# DST800_NMEA2k-CAN_Indicator.net
KiCad netlist of a schematic drawn in Altium Designer
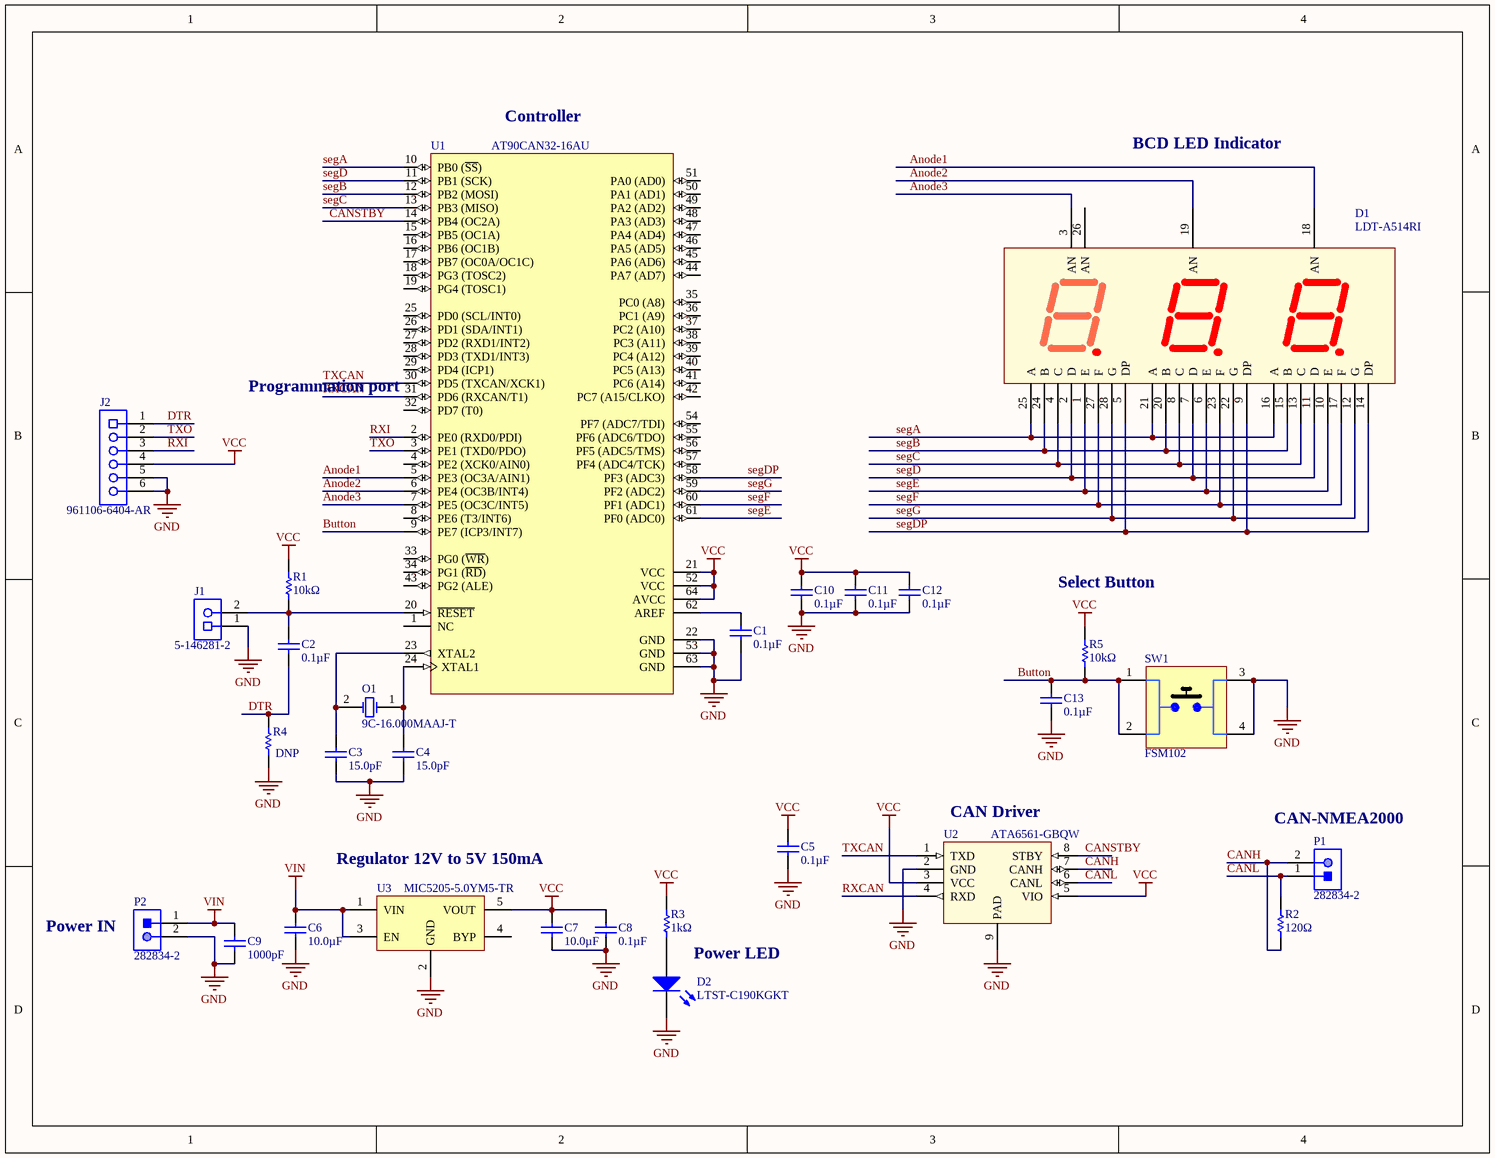
[diagram p0: DST800_NMEA2k-CAN_Indicator.SchDoc]

(export (version "E")
  (design (tool "Eeschema 10.0.6"))
  (components
    (comp (ref "C1")
      (value "0.1µF")
      (footprint "PCB-mhhqftc5ilnrg4qi8ds6-1")
      (description "CAP CER 0.1uF 50V X7R 0603")
      (fields
        (field (name "MANUFACTURER") "Samsung Electro-Mechanics")
        (field (name "MANUFACTURERPARTNUMBER") "CL10B104KB8NNNC")
      )
      (libsource (lib "DST800_NMEA2k-CAN_Indicator") (part "CMP-1af8d38ac64bc53f-5"))
    )
    (comp (ref "C2")
      (value "0.1µF")
      (footprint "PCB-mhhqftc5ilnrg4qi8ds6-1")
      (description "CAP CER 0.1uF 50V X7R 0603")
      (fields
        (field (name "MANUFACTURER") "Samsung Electro-Mechanics")
        (field (name "MANUFACTURERPARTNUMBER") "CL10B104KB8NNNC")
      )
      (libsource (lib "DST800_NMEA2k-CAN_Indicator") (part "CMP-1af8d38ac64bc53f-5"))
    )
    (comp (ref "C3")
      (value "15.0pF")
      (footprint "PCB-69ec8bfnjhyebnpbrrfx-1")
      (description "CAP CER 15pF ±5% 50V C0G/NP0 0603 [1608]")
      (fields
        (field (name "MANUFACTURER") "TDK")
        (field (name "MANUFACTURERPARTNUMBER") "C1608C0G1H150J080AA")
      )
      (libsource (lib "DST800_NMEA2k-CAN_Indicator") (part "CMP-57259fa49f8088e2-2"))
    )
    (comp (ref "C4")
      (value "15.0pF")
      (footprint "PCB-69ec8bfnjhyebnpbrrfx-1")
      (description "CAP CER 15pF ±5% 50V C0G/NP0 0603 [1608]")
      (fields
        (field (name "MANUFACTURER") "TDK")
        (field (name "MANUFACTURERPARTNUMBER") "C1608C0G1H150J080AA")
      )
      (libsource (lib "DST800_NMEA2k-CAN_Indicator") (part "CMP-57259fa49f8088e2-2"))
    )
    (comp (ref "C5")
      (value "0.1µF")
      (footprint "PCB-mhhqftc5ilnrg4qi8ds6-1")
      (description "CAP CER 0.1uF 50V X7R 0603")
      (fields
        (field (name "MANUFACTURER") "Samsung Electro-Mechanics")
        (field (name "MANUFACTURERPARTNUMBER") "CL10B104KB8NNNC")
      )
      (libsource (lib "DST800_NMEA2k-CAN_Indicator") (part "CMP-1af8d38ac64bc53f-5"))
    )
    (comp (ref "C6")
      (value "10.0µF")
      (footprint "PCB-j0jk5xr8qbnaskonccg4-1")
      (description "CAP CER 10uF ±10% 25V X7R 1210")
      (fields
        (field (name "MANUFACTURER") "TDK")
        (field (name "MANUFACTURERPARTNUMBER") "C3225X7R1E106K250AC")
      )
      (libsource (lib "DST800_NMEA2k-CAN_Indicator") (part "CMP-2bdce35de069f41b-1"))
    )
    (comp (ref "C7")
      (value "10.0µF")
      (footprint "PCB-j0jk5xr8qbnaskonccg4-1")
      (description "CAP CER 10uF ±10% 25V X7R 1210")
      (fields
        (field (name "MANUFACTURER") "TDK")
        (field (name "MANUFACTURERPARTNUMBER") "C3225X7R1E106K250AC")
      )
      (libsource (lib "DST800_NMEA2k-CAN_Indicator") (part "CMP-2bdce35de069f41b-1"))
    )
    (comp (ref "C8")
      (value "0.1µF")
      (footprint "PCB-mhhqftc5ilnrg4qi8ds6-1")
      (description "CAP CER 0.1uF 50V X7R 0603")
      (fields
        (field (name "MANUFACTURER") "Samsung Electro-Mechanics")
        (field (name "MANUFACTURERPARTNUMBER") "CL10B104KB8NNNC")
      )
      (libsource (lib "DST800_NMEA2k-CAN_Indicator") (part "CMP-1af8d38ac64bc53f-5"))
    )
    (comp (ref "C9")
      (value "1000pF")
      (footprint "CAPC1608X90X35LL15T15")
      (description "CAP CER 1000pF ±20% 100V X7R 0603")
      (fields (field (name "MANUFACTURERPARTNUMBER") "06031C102MAT2A") (field (name "MANUFACTURER") "AVX"))
      (libsource (lib "DST800_NMEA2k-CAN_Indicator") (part "CMP-126202-2"))
    )
    (comp (ref "C10")
      (value "0.1µF")
      (footprint "PCB-mhhqftc5ilnrg4qi8ds6-1")
      (description "CAP CER 0.1uF 50V X7R 0603")
      (fields
        (field (name "MANUFACTURER") "Samsung Electro-Mechanics")
        (field (name "MANUFACTURERPARTNUMBER") "CL10B104KB8NNNC")
      )
      (libsource (lib "DST800_NMEA2k-CAN_Indicator") (part "CMP-1af8d38ac64bc53f-5"))
    )
    (comp (ref "C11")
      (value "0.1µF")
      (footprint "PCB-mhhqftc5ilnrg4qi8ds6-1")
      (description "CAP CER 0.1uF 50V X7R 0603")
      (fields
        (field (name "MANUFACTURER") "Samsung Electro-Mechanics")
        (field (name "MANUFACTURERPARTNUMBER") "CL10B104KB8NNNC")
      )
      (libsource (lib "DST800_NMEA2k-CAN_Indicator") (part "CMP-1af8d38ac64bc53f-5"))
    )
    (comp (ref "C12")
      (value "0.1µF")
      (footprint "PCB-mhhqftc5ilnrg4qi8ds6-1")
      (description "CAP CER 0.1uF 50V X7R 0603")
      (fields
        (field (name "MANUFACTURER") "Samsung Electro-Mechanics")
        (field (name "MANUFACTURERPARTNUMBER") "CL10B104KB8NNNC")
      )
      (libsource (lib "DST800_NMEA2k-CAN_Indicator") (part "CMP-1af8d38ac64bc53f-5"))
    )
    (comp (ref "C13")
      (value "0.1µF")
      (footprint "PCB-mhhqftc5ilnrg4qi8ds6-1")
      (description "CAP CER 0.1uF 50V X7R 0603")
      (fields
        (field (name "MANUFACTURER") "Samsung Electro-Mechanics")
        (field (name "MANUFACTURERPARTNUMBER") "CL10B104KB8NNNC")
      )
      (libsource (lib "DST800_NMEA2k-CAN_Indicator") (part "CMP-1af8d38ac64bc53f-5"))
    )
    (comp (ref "D1")
      (value "LDT-A514RI")
      (footprint "LDTA514RI")
      (description "Display 3-digit 7-Seg 0.56 in")
      (fields (field (name "MANUFACTURER") "Lumex"))
      (libsource (lib "DST800_NMEA2k-CAN_Indicator") (part "CMP-6dbba4b18441b27c-1"))
    )
    (comp (ref "D2")
      (value "LTST-C190KGKT")
      (footprint "PCB-eapfwhp0rnksgujf96h3-1")
      (description "LED 0603 green")
      (fields (field (name "MANUFACTURER") "Lite-On"))
      (libsource (lib "DST800_NMEA2k-CAN_Indicator") (part "CMP-e1642866a00b3ea3-3"))
    )
    (comp (ref "J1")
      (value "5-146281-2")
      (footprint "PCB-angfy19quc8nc8nc7d0m-1")
      (description "CONN HEADER VERT 2POS Single 0.1in pitch")
      (fields (field (name "MANUFACTURER") "TE Connectivity"))
      (libsource (lib "DST800_NMEA2k-CAN_Indicator") (part "CMP-39c9f206a0b6e60e-14"))
    )
    (comp (ref "J2")
      (value "961106-6404-AR")
      (footprint "PCB-660833-1")
      (description "CONN HEADER VERT 6POS Single 0.1in pitch")
      (fields (field (name "MANUFACTURER") "3M"))
      (libsource (lib "DST800_NMEA2k-CAN_Indicator") (part "CMP-660833-2"))
    )
    (comp (ref "O1")
      (value "9C-16.000MAAJ-T")
      (footprint "PCB-3qvzojcyidn2gltqqmbl-1")
      (description "Crystal 16MHz 30ppm  18pF  HC-49/S SMD")
      (fields (field (name "MANUFACTURER") "TXC CORPORATION"))
      (libsource (lib "DST800_NMEA2k-CAN_Indicator") (part "CMP-df271731c43900e0-3"))
    )
    (comp (ref "P1")
      (value "282834-2")
      (footprint "PCB-0kdx5sneyudsmu18l6zv-1")
      (description "CONN Terminal Block; 16-30 AWG 0.197 in")
      (fields (field (name "MANUFACTURER") "TE Connectivity"))
      (libsource (lib "DST800_NMEA2k-CAN_Indicator") (part "CMP-369bfdc835bbe95c-32"))
    )
    (comp (ref "P2")
      (value "282834-2")
      (footprint "PCB-0kdx5sneyudsmu18l6zv-1")
      (description "CONN Terminal Block; 16-30 AWG 0.197 in")
      (fields (field (name "MANUFACTURER") "TE Connectivity"))
      (libsource (lib "") (part "CMP-369bfdc835bbe95c-32_1"))
    )
    (comp (ref "R1")
      (value "10kΩ")
      (footprint "RESC1608X55X30NL15T15")
      (description "RES 10K 1% 0.1W 0603")
      (fields
        (field (name "MANUFACTURERPARTNUMBER") "CRG0603F10K")
        (field (name "MANUFACTURER") "TE Connectivity")
      )
      (libsource (lib "DST800_NMEA2k-CAN_Indicator") (part "CMP-584891b72cc4878f-2"))
    )
    (comp (ref "R2")
      (value "120Ω")
      (footprint "RESC3216X60X45LL10T20")
      (description "RES Thick Film 120ohm 5% 1/4W 1206")
      (fields
        (field (name "MANUFACTURERPARTNUMBER") "CRCW1206120RJNEA")
        (field (name "MANUFACTURER") "Vishay")
      )
      (libsource (lib "DST800_NMEA2k-CAN_Indicator") (part "CMP-1858100-4"))
    )
    (comp (ref "R3")
      (value "1kΩ")
      (footprint "RESC1608X55X30NL20T20")
      (description "RES Metal Film 1Kohm 0.1%  0603")
      (fields
        (field (name "MANUFACTURERPARTNUMBER") "ERA-3YEB102V")
        (field (name "MANUFACTURER") "Panasonic")
      )
      (libsource (lib "DST800_NMEA2k-CAN_Indicator") (part "CMP-3717598-2"))
    )
    (comp (ref "R4")
      (value "DNP")
      (footprint "RESC1608X55X30NL20T20")
      (description "RES Metal Film 1Kohm 0.1%  0603")
      (fields
        (field (name "MANUFACTURERPARTNUMBER") "ERA-3YEB102V")
        (field (name "MANUFACTURER") "Panasonic")
      )
      (libsource (lib "DST800_NMEA2k-CAN_Indicator") (part "CMP-3717598-2"))
    )
    (comp (ref "R5")
      (value "10kΩ")
      (footprint "RESC1608X55X30NL15T15")
      (description "RES 10K 1% 0.1W 0603")
      (fields
        (field (name "MANUFACTURERPARTNUMBER") "CRG0603F10K")
        (field (name "MANUFACTURER") "TE Connectivity")
      )
      (libsource (lib "DST800_NMEA2k-CAN_Indicator") (part "CMP-584891b72cc4878f-2"))
    )
    (comp (ref "SW1")
      (value "FSM102")
      (footprint "PCB-8ps4wla3pj92cxv2yuvu-1")
      (description "PUSHBUTTON Momentary Tactile SPST Thru-Hole")
      (fields (field (name "MANUFACTURER") "TE Connectivity"))
      (libsource (lib "DST800_NMEA2k-CAN_Indicator") (part "CMP-43e488b0e8c29c23-11"))
    )
    (comp (ref "U1")
      (value "AT90CAN32-16AU")
      (footprint "64A_L")
      (description "IC Microcontroller 8-bit AVR 32KB Flash CAN Controller 53GPIO 64-pin LQFP")
      (fields (field (name "MANUFACTURER") "Microchip"))
      (libsource (lib "DST800_NMEA2k-CAN_Indicator") (part "CMP-972593-3"))
    )
    (comp (ref "U2")
      (value "ATA6561-GBQW")
      (footprint "PCB_8-PinVDFN")
      (description "IC Transeiver CAN 5Mbps 8-Pin VDFN EP")
      (fields (field (name "MANUFACTURER") "Microchip"))
      (libsource (lib "DST800_NMEA2k-CAN_Indicator") (part "CMP-9a565056add04591-7"))
    )
    (comp (ref "U3")
      (value "MIC5205-5.0YM5-TR")
      (footprint "SOT-23-5_N")
      (description "IC Regulator LDO 5 V Fixed Output 150 mA SOT-23-5")
      (fields (field (name "MANUFACTURER") "Microchip"))
      (libsource (lib "DST800_NMEA2k-CAN_Indicator") (part "CMP-6255a8a416e5bd92-5"))
    )
  )
  (nets
    (net (code "1") (name "/Anode1") (class "Default")
      (node (ref "D1") (pin "18") (pinfunction "AN_18") (pintype "passive"))
      (node (ref "U1") (pin "5") (pinfunction "PE3_(OC3A/AIN1)_5") (pintype "bidirectional"))
    )
    (net (code "2") (name "/Anode2") (class "Default")
      (node (ref "D1") (pin "19") (pinfunction "AN_19") (pintype "passive"))
      (node (ref "U1") (pin "6") (pinfunction "PE4_(OC3B/INT4)_6") (pintype "bidirectional"))
    )
    (net (code "3") (name "/Anode3") (class "Default")
      (node (ref "D1") (pin "3") (pinfunction "AN_3") (pintype "passive"))
      (node (ref "U1") (pin "7") (pinfunction "PE5_(OC3C/INT5)_7") (pintype "bidirectional"))
    )
    (net (code "4") (name "/Button") (class "Default")
      (node (ref "C13") (pin "2") (pinfunction "2_2") (pintype "passive"))
      (node (ref "R5") (pin "1") (pinfunction "1_1") (pintype "passive"))
      (node (ref "SW1") (pin "1") (pinfunction "1_1") (pintype "passive"))
      (node (ref "SW1") (pin "2") (pinfunction "2_2") (pintype "passive"))
      (node (ref "U1") (pin "9") (pinfunction "PE7_(ICP3/INT7)_9") (pintype "bidirectional"))
    )
    (net (code "5") (name "/CANH") (class "Default")
      (node (ref "P1") (pin "2") (pinfunction "2_2") (pintype "passive"))
      (node (ref "R2") (pin "1") (pinfunction "1_1") (pintype "passive"))
      (node (ref "U2") (pin "7") (pinfunction "CANH_7") (pintype "bidirectional"))
    )
    (net (code "6") (name "/CANL") (class "Default")
      (node (ref "P1") (pin "1") (pinfunction "1_1") (pintype "passive"))
      (node (ref "R2") (pin "2") (pinfunction "2_2") (pintype "passive"))
      (node (ref "U2") (pin "6") (pinfunction "CANL_6") (pintype "bidirectional"))
    )
    (net (code "7") (name "/CANSTBY") (class "Default")
      (node (ref "U1") (pin "14") (pinfunction "PB4_(OC2A)_14") (pintype "bidirectional"))
      (node (ref "U2") (pin "8") (pinfunction "STBY_8") (pintype "input"))
    )
    (net (code "8") (name "/DTR") (class "Default")
      (node (ref "C2") (pin "1") (pinfunction "1_1") (pintype "passive"))
      (node (ref "J2") (pin "1") (pinfunction "1_1") (pintype "passive"))
      (node (ref "R4") (pin "2") (pinfunction "2_2") (pintype "passive"))
    )
    (net (code "9") (name "/RXCAN") (class "Default")
      (node (ref "U1") (pin "31") (pinfunction "PD6_(RXCAN/T1)_31") (pintype "bidirectional"))
      (node (ref "U2") (pin "4") (pinfunction "RXD_4") (pintype "output"))
    )
    (net (code "10") (name "/RXI") (class "Default")
      (node (ref "J2") (pin "3") (pinfunction "3_3") (pintype "passive"))
      (node (ref "U1") (pin "2") (pinfunction "PE0_(RXD0/PDI)_2") (pintype "bidirectional"))
    )
    (net (code "11") (name "/TXCAN") (class "Default")
      (node (ref "U1") (pin "30") (pinfunction "PD5_(TXCAN/XCK1)_30") (pintype "bidirectional"))
      (node (ref "U2") (pin "1") (pinfunction "TXD_1") (pintype "input"))
    )
    (net (code "12") (name "/TXO") (class "Default")
      (node (ref "J2") (pin "2") (pinfunction "2_2") (pintype "passive"))
      (node (ref "U1") (pin "3") (pinfunction "PE1_(TXD0/PDO)_3") (pintype "bidirectional"))
    )
    (net (code "13") (name "/segA") (class "Default")
      (node (ref "D1") (pin "16") (pinfunction "A_16") (pintype "passive"))
      (node (ref "D1") (pin "21") (pinfunction "A_21") (pintype "passive"))
      (node (ref "D1") (pin "25") (pinfunction "A_25") (pintype "passive"))
      (node (ref "U1") (pin "10") (pinfunction "PB0_(~{SS})_10") (pintype "bidirectional"))
    )
    (net (code "14") (name "/segB") (class "Default")
      (node (ref "D1") (pin "15") (pinfunction "B_15") (pintype "passive"))
      (node (ref "D1") (pin "20") (pinfunction "B_20") (pintype "passive"))
      (node (ref "D1") (pin "24") (pinfunction "B_24") (pintype "passive"))
      (node (ref "U1") (pin "12") (pinfunction "PB2_(MOSI)_12") (pintype "bidirectional"))
    )
    (net (code "15") (name "/segC") (class "Default")
      (node (ref "D1") (pin "13") (pinfunction "C_13") (pintype "passive"))
      (node (ref "D1") (pin "4") (pinfunction "C_4") (pintype "passive"))
      (node (ref "D1") (pin "8") (pinfunction "C_8") (pintype "passive"))
      (node (ref "U1") (pin "13") (pinfunction "PB3_(MISO)_13") (pintype "bidirectional"))
    )
    (net (code "16") (name "/segD") (class "Default")
      (node (ref "D1") (pin "11") (pinfunction "D_11") (pintype "passive"))
      (node (ref "D1") (pin "2") (pinfunction "D_2") (pintype "passive"))
      (node (ref "D1") (pin "7") (pinfunction "D_7") (pintype "passive"))
      (node (ref "U1") (pin "11") (pinfunction "PB1_(SCK)_11") (pintype "bidirectional"))
    )
    (net (code "17") (name "/segDP") (class "Default")
      (node (ref "D1") (pin "14") (pinfunction "DP_14") (pintype "passive"))
      (node (ref "D1") (pin "5") (pinfunction "DP_5") (pintype "passive"))
      (node (ref "D1") (pin "9") (pinfunction "DP_9") (pintype "passive"))
      (node (ref "U1") (pin "58") (pinfunction "PF3_(ADC3)_58") (pintype "bidirectional"))
    )
    (net (code "18") (name "/segE") (class "Default")
      (node (ref "D1") (pin "1") (pinfunction "E_1") (pintype "passive"))
      (node (ref "D1") (pin "10") (pinfunction "E_10") (pintype "passive"))
      (node (ref "D1") (pin "6") (pinfunction "E_6") (pintype "passive"))
      (node (ref "U1") (pin "61") (pinfunction "PF0_(ADC0)_61") (pintype "bidirectional"))
    )
    (net (code "19") (name "/segF") (class "Default")
      (node (ref "D1") (pin "17") (pinfunction "F_17") (pintype "passive"))
      (node (ref "D1") (pin "23") (pinfunction "F_23") (pintype "passive"))
      (node (ref "D1") (pin "27") (pinfunction "F_27") (pintype "passive"))
      (node (ref "U1") (pin "60") (pinfunction "PF1_(ADC1)_60") (pintype "bidirectional"))
    )
    (net (code "20") (name "/segG") (class "Default")
      (node (ref "D1") (pin "12") (pinfunction "G_12") (pintype "passive"))
      (node (ref "D1") (pin "22") (pinfunction "G_22") (pintype "passive"))
      (node (ref "D1") (pin "28") (pinfunction "G_28") (pintype "passive"))
      (node (ref "U1") (pin "59") (pinfunction "PF2_(ADC2)_59") (pintype "bidirectional"))
    )
    (net (code "21") (name "GND") (class "Default")
      (node (ref "C1") (pin "1") (pinfunction "1_1") (pintype "passive"))
      (node (ref "C10") (pin "1") (pinfunction "1_1") (pintype "passive"))
      (node (ref "C11") (pin "1") (pinfunction "1_1") (pintype "passive"))
      (node (ref "C12") (pin "1") (pinfunction "1_1") (pintype "passive"))
      (node (ref "C13") (pin "1") (pinfunction "1_1") (pintype "passive"))
      (node (ref "C3") (pin "1") (pinfunction "1_1") (pintype "passive"))
      (node (ref "C4") (pin "1") (pinfunction "1_1") (pintype "passive"))
      (node (ref "C5") (pin "1") (pinfunction "1_1") (pintype "passive"))
      (node (ref "C6") (pin "1") (pinfunction "1_1") (pintype "passive"))
      (node (ref "C7") (pin "1") (pinfunction "1_1") (pintype "passive"))
      (node (ref "C8") (pin "1") (pinfunction "1_1") (pintype "passive"))
      (node (ref "C9") (pin "1") (pinfunction "1_1") (pintype "passive"))
      (node (ref "D2") (pin "2") (pinfunction "K_2") (pintype "passive"))
      (node (ref "J1") (pin "1") (pinfunction "1_1") (pintype "passive"))
      (node (ref "J2") (pin "5") (pinfunction "5_5") (pintype "passive"))
      (node (ref "J2") (pin "6") (pinfunction "6_6") (pintype "passive"))
      (node (ref "P2") (pin "2") (pinfunction "2_2") (pintype "passive"))
      (node (ref "R4") (pin "1") (pinfunction "1_1") (pintype "passive"))
      (node (ref "SW1") (pin "3") (pinfunction "3_3") (pintype "passive"))
      (node (ref "SW1") (pin "4") (pinfunction "4_4") (pintype "passive"))
      (node (ref "U1") (pin "22") (pinfunction "GND_22") (pintype "power_in"))
      (node (ref "U1") (pin "53") (pinfunction "GND_53") (pintype "power_in"))
      (node (ref "U1") (pin "63") (pinfunction "GND_63") (pintype "power_in"))
      (node (ref "U2") (pin "2") (pinfunction "GND_2") (pintype "power_in"))
      (node (ref "U2") (pin "9") (pinfunction "PAD_9") (pintype "power_in"))
      (node (ref "U3") (pin "2") (pinfunction "GND_2") (pintype "passive"))
    )
    (net (code "22") (name "Net-(D2-A)") (class "Default")
      (node (ref "D2") (pin "1") (pinfunction "A_1") (pintype "passive"))
      (node (ref "R3") (pin "1") (pinfunction "1_1") (pintype "passive"))
    )
    (net (code "23") (name "Net-(O1-X1)") (class "Default")
      (node (ref "C4") (pin "2") (pinfunction "2_2") (pintype "passive"))
      (node (ref "O1") (pin "1") (pinfunction "X1_1") (pintype "passive"))
      (node (ref "U1") (pin "24") (pinfunction "XTAL1_24") (pintype "input"))
    )
    (net (code "24") (name "Net-(O1-X2)") (class "Default")
      (node (ref "C3") (pin "2") (pinfunction "2_2") (pintype "passive"))
      (node (ref "O1") (pin "2") (pinfunction "X2_2") (pintype "passive"))
      (node (ref "U1") (pin "23") (pinfunction "XTAL2_23") (pintype "output"))
    )
    (net (code "25") (name "Net-(U1-AREF)") (class "Default")
      (node (ref "C1") (pin "2") (pinfunction "2_2") (pintype "passive"))
      (node (ref "U1") (pin "62") (pinfunction "AREF_62") (pintype "power_in"))
    )
    (net (code "26") (name "Net-(U1-~{RESET})") (class "Default")
      (node (ref "C2") (pin "2") (pinfunction "2_2") (pintype "passive"))
      (node (ref "J1") (pin "2") (pinfunction "2_2") (pintype "passive"))
      (node (ref "R1") (pin "1") (pinfunction "1_1") (pintype "passive"))
      (node (ref "U1") (pin "20") (pinfunction "~{RESET}_20") (pintype "input"))
    )
    (net (code "27") (name "VCC") (class "Default")
      (node (ref "C10") (pin "2") (pinfunction "2_2") (pintype "passive"))
      (node (ref "C11") (pin "2") (pinfunction "2_2") (pintype "passive"))
      (node (ref "C12") (pin "2") (pinfunction "2_2") (pintype "passive"))
      (node (ref "C5") (pin "2") (pinfunction "2_2") (pintype "passive"))
      (node (ref "C7") (pin "2") (pinfunction "2_2") (pintype "passive"))
      (node (ref "C8") (pin "2") (pinfunction "2_2") (pintype "passive"))
      (node (ref "J2") (pin "4") (pinfunction "4_4") (pintype "passive"))
      (node (ref "R1") (pin "2") (pinfunction "2_2") (pintype "passive"))
      (node (ref "R3") (pin "2") (pinfunction "2_2") (pintype "passive"))
      (node (ref "R5") (pin "2") (pinfunction "2_2") (pintype "passive"))
      (node (ref "U1") (pin "21") (pinfunction "VCC_21") (pintype "power_in"))
      (node (ref "U1") (pin "52") (pinfunction "VCC_52") (pintype "power_in"))
      (node (ref "U1") (pin "64") (pinfunction "AVCC_64") (pintype "power_in"))
      (node (ref "U2") (pin "3") (pinfunction "VCC_3") (pintype "power_in"))
      (node (ref "U2") (pin "5") (pinfunction "VIO_5") (pintype "input"))
      (node (ref "U3") (pin "5") (pinfunction "VOUT_5") (pintype "passive"))
    )
    (net (code "28") (name "VIN") (class "Default")
      (node (ref "C6") (pin "2") (pinfunction "2_2") (pintype "passive"))
      (node (ref "C9") (pin "2") (pinfunction "2_2") (pintype "passive"))
      (node (ref "P2") (pin "1") (pinfunction "1_1") (pintype "passive"))
      (node (ref "U3") (pin "1") (pinfunction "VIN_1") (pintype "passive"))
      (node (ref "U3") (pin "3") (pinfunction "EN_3") (pintype "passive"))
    )
    (net (code "29") (name "unconnected-(D1-AN-Pad26)") (class "Default")
      (node (ref "D1") (pin "26") (pinfunction "AN_26") (pintype "passive"))
    )
    (net (code "30") (name "unconnected-(U1-NC-Pad1)") (class "Default")
      (node (ref "U1") (pin "1") (pinfunction "NC_1") (pintype "passive"))
    )
    (net (code "31") (name "unconnected-(U1-PA0_(AD0)-Pad51)") (class "Default")
      (node (ref "U1") (pin "51") (pinfunction "PA0_(AD0)_51") (pintype "bidirectional"))
    )
    (net (code "32") (name "unconnected-(U1-PA1_(AD1)-Pad50)") (class "Default")
      (node (ref "U1") (pin "50") (pinfunction "PA1_(AD1)_50") (pintype "bidirectional"))
    )
    (net (code "33") (name "unconnected-(U1-PA2_(AD2)-Pad49)") (class "Default")
      (node (ref "U1") (pin "49") (pinfunction "PA2_(AD2)_49") (pintype "bidirectional"))
    )
    (net (code "34") (name "unconnected-(U1-PA3_(AD3)-Pad48)") (class "Default")
      (node (ref "U1") (pin "48") (pinfunction "PA3_(AD3)_48") (pintype "bidirectional"))
    )
    (net (code "35") (name "unconnected-(U1-PA4_(AD4)-Pad47)") (class "Default")
      (node (ref "U1") (pin "47") (pinfunction "PA4_(AD4)_47") (pintype "bidirectional"))
    )
    (net (code "36") (name "unconnected-(U1-PA5_(AD5)-Pad46)") (class "Default")
      (node (ref "U1") (pin "46") (pinfunction "PA5_(AD5)_46") (pintype "bidirectional"))
    )
    (net (code "37") (name "unconnected-(U1-PA6_(AD6)-Pad45)") (class "Default")
      (node (ref "U1") (pin "45") (pinfunction "PA6_(AD6)_45") (pintype "bidirectional"))
    )
    (net (code "38") (name "unconnected-(U1-PA7_(AD7)-Pad44)") (class "Default")
      (node (ref "U1") (pin "44") (pinfunction "PA7_(AD7)_44") (pintype "bidirectional"))
    )
    (net (code "39") (name "unconnected-(U1-PB5_(OC1A)-Pad15)") (class "Default")
      (node (ref "U1") (pin "15") (pinfunction "PB5_(OC1A)_15") (pintype "bidirectional"))
    )
    (net (code "40") (name "unconnected-(U1-PB6_(OC1B)-Pad16)") (class "Default")
      (node (ref "U1") (pin "16") (pinfunction "PB6_(OC1B)_16") (pintype "bidirectional"))
    )
    (net (code "41") (name "unconnected-(U1-PB7_(OC0A{slash}OC1C)-Pad17)") (class "Default")
      (node (ref "U1") (pin "17") (pinfunction "PB7_(OC0A/OC1C)_17") (pintype "bidirectional"))
    )
    (net (code "42") (name "unconnected-(U1-PC0_(A8)-Pad35)") (class "Default")
      (node (ref "U1") (pin "35") (pinfunction "PC0_(A8)_35") (pintype "bidirectional"))
    )
    (net (code "43") (name "unconnected-(U1-PC1_(A9)-Pad36)") (class "Default")
      (node (ref "U1") (pin "36") (pinfunction "PC1_(A9)_36") (pintype "bidirectional"))
    )
    (net (code "44") (name "unconnected-(U1-PC2_(A10)-Pad37)") (class "Default")
      (node (ref "U1") (pin "37") (pinfunction "PC2_(A10)_37") (pintype "bidirectional"))
    )
    (net (code "45") (name "unconnected-(U1-PC3_(A11)-Pad38)") (class "Default")
      (node (ref "U1") (pin "38") (pinfunction "PC3_(A11)_38") (pintype "bidirectional"))
    )
    (net (code "46") (name "unconnected-(U1-PC4_(A12)-Pad39)") (class "Default")
      (node (ref "U1") (pin "39") (pinfunction "PC4_(A12)_39") (pintype "bidirectional"))
    )
    (net (code "47") (name "unconnected-(U1-PC5_(A13)-Pad40)") (class "Default")
      (node (ref "U1") (pin "40") (pinfunction "PC5_(A13)_40") (pintype "bidirectional"))
    )
    (net (code "48") (name "unconnected-(U1-PC6_(A14)-Pad41)") (class "Default")
      (node (ref "U1") (pin "41") (pinfunction "PC6_(A14)_41") (pintype "bidirectional"))
    )
    (net (code "49") (name "unconnected-(U1-PC7_(A15{slash}CLKO)-Pad42)") (class "Default")
      (node (ref "U1") (pin "42") (pinfunction "PC7_(A15/CLKO)_42") (pintype "bidirectional"))
    )
    (net (code "50") (name "unconnected-(U1-PD0_(SCL{slash}INT0)-Pad25)") (class "Default")
      (node (ref "U1") (pin "25") (pinfunction "PD0_(SCL/INT0)_25") (pintype "bidirectional"))
    )
    (net (code "51") (name "unconnected-(U1-PD1_(SDA{slash}INT1)-Pad26)") (class "Default")
      (node (ref "U1") (pin "26") (pinfunction "PD1_(SDA/INT1)_26") (pintype "bidirectional"))
    )
    (net (code "52") (name "unconnected-(U1-PD2_(RXD1{slash}INT2)-Pad27)") (class "Default")
      (node (ref "U1") (pin "27") (pinfunction "PD2_(RXD1/INT2)_27") (pintype "bidirectional"))
    )
    (net (code "53") (name "unconnected-(U1-PD3_(TXD1{slash}INT3)-Pad28)") (class "Default")
      (node (ref "U1") (pin "28") (pinfunction "PD3_(TXD1/INT3)_28") (pintype "bidirectional"))
    )
    (net (code "54") (name "unconnected-(U1-PD4_(ICP1)-Pad29)") (class "Default")
      (node (ref "U1") (pin "29") (pinfunction "PD4_(ICP1)_29") (pintype "bidirectional"))
    )
    (net (code "55") (name "unconnected-(U1-PD7_(T0)-Pad32)") (class "Default")
      (node (ref "U1") (pin "32") (pinfunction "PD7_(T0)_32") (pintype "bidirectional"))
    )
    (net (code "56") (name "unconnected-(U1-PE2_(XCK0{slash}AIN0)-Pad4)") (class "Default")
      (node (ref "U1") (pin "4") (pinfunction "PE2_(XCK0/AIN0)_4") (pintype "bidirectional"))
    )
    (net (code "57") (name "unconnected-(U1-PE6_(T3{slash}INT6)-Pad8)") (class "Default")
      (node (ref "U1") (pin "8") (pinfunction "PE6_(T3/INT6)_8") (pintype "bidirectional"))
    )
    (net (code "58") (name "unconnected-(U1-PF4_(ADC4{slash}TCK)-Pad57)") (class "Default")
      (node (ref "U1") (pin "57") (pinfunction "PF4_(ADC4/TCK)_57") (pintype "bidirectional"))
    )
    (net (code "59") (name "unconnected-(U1-PF5_(ADC5{slash}TMS)-Pad56)") (class "Default")
      (node (ref "U1") (pin "56") (pinfunction "PF5_(ADC5/TMS)_56") (pintype "bidirectional"))
    )
    (net (code "60") (name "unconnected-(U1-PF6_(ADC6{slash}TDO)-Pad55)") (class "Default")
      (node (ref "U1") (pin "55") (pinfunction "PF6_(ADC6/TDO)_55") (pintype "bidirectional"))
    )
    (net (code "61") (name "unconnected-(U1-PF7_(ADC7{slash}TDI)-Pad54)") (class "Default")
      (node (ref "U1") (pin "54") (pinfunction "PF7_(ADC7/TDI)_54") (pintype "bidirectional"))
    )
    (net (code "62") (name "unconnected-(U1-PG0_(~{WR})-Pad33)") (class "Default")
      (node (ref "U1") (pin "33") (pinfunction "PG0_(~{WR})_33") (pintype "bidirectional"))
    )
    (net (code "63") (name "unconnected-(U1-PG1_(~{RD})-Pad34)") (class "Default")
      (node (ref "U1") (pin "34") (pinfunction "PG1_(~{RD})_34") (pintype "bidirectional"))
    )
    (net (code "64") (name "unconnected-(U1-PG2_(ALE)-Pad43)") (class "Default")
      (node (ref "U1") (pin "43") (pinfunction "PG2_(ALE)_43") (pintype "bidirectional"))
    )
    (net (code "65") (name "unconnected-(U1-PG3_(TOSC2)-Pad18)") (class "Default")
      (node (ref "U1") (pin "18") (pinfunction "PG3_(TOSC2)_18") (pintype "bidirectional"))
    )
    (net (code "66") (name "unconnected-(U1-PG4_(TOSC1)-Pad19)") (class "Default")
      (node (ref "U1") (pin "19") (pinfunction "PG4_(TOSC1)_19") (pintype "bidirectional"))
    )
    (net (code "67") (name "unconnected-(U3-BYP-Pad4)") (class "Default")
      (node (ref "U3") (pin "4") (pinfunction "BYP_4") (pintype "passive"))
    )
  )
)
